# merigold.net
KiCad netlist of a schematic drawn in Altium Designer
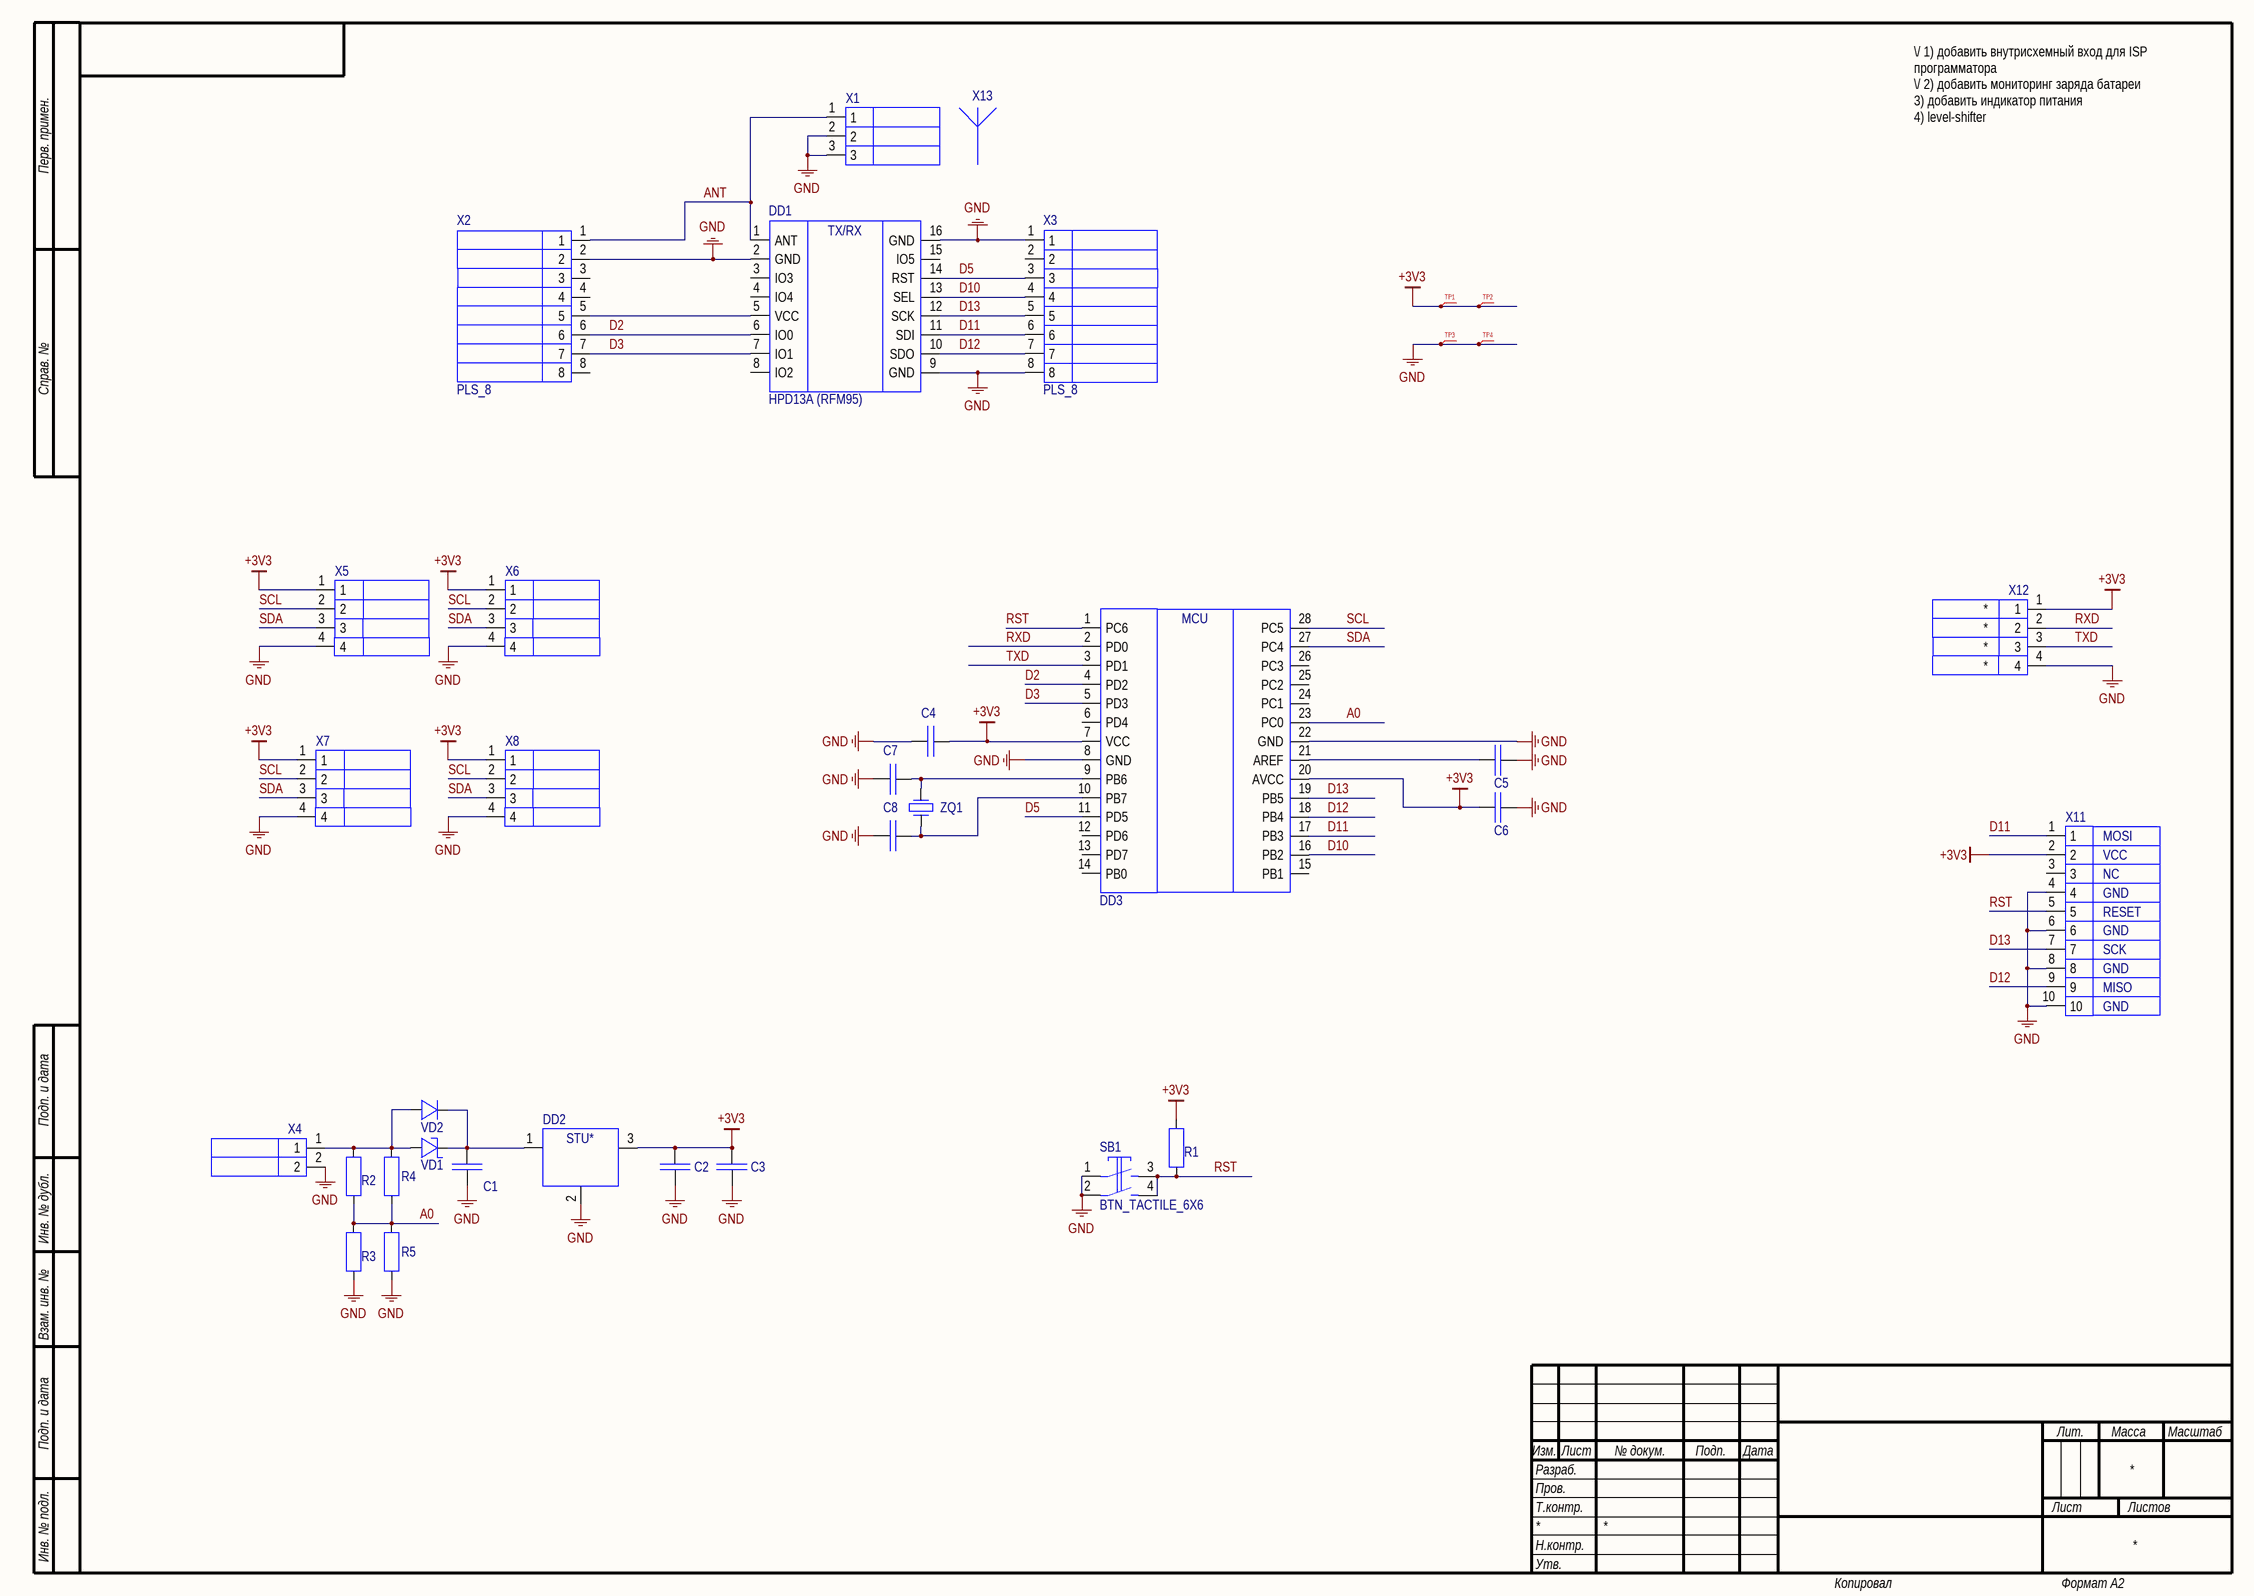
[diagram p0: merigold.SchDoc]

(export (version "E")
  (design (tool "Eeschema 10.0.6"))
  (components
    (comp (ref "C1")
      (value "10U10V_CAPC")
      (footprint "CAPC2012X14M/0805")
      (description "CAP CER 10UF 10V X5R 0805")
      (fields
        (field (name "MANUFACTURER") "Samsung Electro-Mechanics")
        (field (name "MANUFACTURER PART NUMBER") "CL21A106KPFNNNG")
      )
      (libsource (lib "C") (part "10U10V_CAPC"))
    )
    (comp (ref "C2")
      (value "10U10V_CAPC")
      (footprint "CAPC2012X14M/0805")
      (description "CAP CER 10UF 10V X5R 0805")
      (fields
        (field (name "MANUFACTURER") "Samsung Electro-Mechanics")
        (field (name "MANUFACTURER PART NUMBER") "CL21A106KPFNNNG")
      )
      (libsource (lib "C") (part "10U10V_CAPC"))
    )
    (comp (ref "C3")
      (value "1U16V_CAPC")
      (footprint "CAPC2012X14M/0805")
      (description "CAP CER 1UF 16V X7R 0805")
      (fields
        (field (name "MANUFACTURER") "Murata Manufacturing")
        (field (name "MANUFACTURER PART NUMBER") "GRM21BR71C105KA01K")
      )
      (libsource (lib "C") (part "1U16V_CAPC"))
    )
    (comp (ref "C4")
      (value "1U16V_CAPC")
      (footprint "CAPC2012X14M/0805")
      (description "CAP CER 1UF 16V X7R 0805")
      (fields
        (field (name "MANUFACTURER") "Murata Manufacturing")
        (field (name "MANUFACTURER PART NUMBER") "GRM21BR71C105KA01K")
      )
      (libsource (lib "C") (part "1U16V_CAPC"))
    )
    (comp (ref "C5")
      (value "1U16V_CAPC")
      (footprint "CAPC2012X14M/0805")
      (description "CAP CER 1UF 16V X7R 0805")
      (fields
        (field (name "MANUFACTURER") "Murata Manufacturing")
        (field (name "MANUFACTURER PART NUMBER") "GRM21BR71C105KA01K")
      )
      (libsource (lib "C") (part "1U16V_CAPC"))
    )
    (comp (ref "C6")
      (value "1U16V_CAPC")
      (footprint "CAPC2012X14M/0805")
      (description "CAP CER 1UF 16V X7R 0805")
      (fields
        (field (name "MANUFACTURER") "Murata Manufacturing")
        (field (name "MANUFACTURER PART NUMBER") "GRM21BR71C105KA01K")
      )
      (libsource (lib "C") (part "1U16V_CAPC"))
    )
    (comp (ref "C7")
      (value "22P250V_CAPC")
      (footprint "CAPC2012X14M/0805")
      (description "CAP CER 22PF 250V C0G/NP0 0805")
      (fields
        (field (name "MANUFACTURER") "Murata Manufacturing")
        (field (name "MANUFACTURER PART NUMBER") "GRM21A5C2E220JW01")
      )
      (libsource (lib "C") (part "22P250V_CAPC"))
    )
    (comp (ref "C8")
      (value "22P250V_CAPC")
      (footprint "CAPC2012X14M/0805")
      (description "CAP CER 22PF 250V C0G/NP0 0805")
      (fields
        (field (name "MANUFACTURER") "Murata Manufacturing")
        (field (name "MANUFACTURER PART NUMBER") "GRM21A5C2E220JW01")
      )
      (libsource (lib "C") (part "22P250V_CAPC"))
    )
    (comp (ref "DD1")
      (value "HPD13A (RFM95)")
      (footprint "IC:SOJ200P1600X200-16M")
      (description "RF TXRX MODULE ISM<1GHZ")
      (fields
        (field (name "MANUFACTURER") "RF Solutions")
        (field (name "MANUFACTURER PART NUMBER") "RFM95W-868S2")
      )
      (libsource (lib "IC") (part "HPD13A (RFM95)"))
    )
    (comp (ref "DD2")
      (value "LM1117MPX-3.3/NOPB")
      (footprint "SOT230P700X180-4M")
      (description "IC REG LIN 3.3V 800MA SOT223-4")
      (fields (field (name "MANUFACTURER") "Texas Instruments"))
      (libsource (lib "IC") (part "AMS1117"))
    )
    (comp (ref "DD3")
      (value "ATMEGA328")
      (footprint "PDIP28")
      (description "IC MCU 8BIT 32KB FLASH 28DIP")
      (fields
        (field (name "MANUFACTURER") "Microchip / Atmel")
        (field (name "MANUFACTURER PART NUMBER") "ATMEGA328P-PU")
      )
      (libsource (lib "IC") (part "ATMEGA328P-PU"))
    )
    (comp (ref "R1")
      (value "10K1206")
      (footprint "RLC:RESC3216X07N/1206")
      (description "RES SMD 10K OHM 1% 1/4W 1206")
      (fields
        (field (name "MANUFACTURER") "Panasonic")
        (field (name "MANUFACTURER PART NUMBER") "ERJ8ENF1002V")
      )
      (libsource (lib "R") (part "10K1206"))
    )
    (comp (ref "R2")
      (value "RNF14FTD100K")
      (footprint "RESAD800W55L600D230")
      (description "RES 100K OHM 1/4W 5% AXIAL")
      (fields (field (name "MANUFACTURER") "Stackpole Electronics"))
      (libsource (lib "R") (part "100K_AD800W55L600D230"))
    )
    (comp (ref "R3")
      (value "RNF14FTD100K")
      (footprint "RESAD800W55L600D230")
      (description "RES 100K OHM 1/4W 5% AXIAL")
      (fields (field (name "MANUFACTURER") "Stackpole Electronics"))
      (libsource (lib "R") (part "100K_AD800W55L600D230"))
    )
    (comp (ref "R4")
      (value "100K0603")
      (footprint "RESC1608X06N/0603")
      (description "RES SMD 100K OHM 1% 1/4W 0603")
      (fields (field (name "MANUFACTURER PART NUMBER") "ESR03EZPF1003"))
      (libsource (lib "R") (part "100K0603"))
    )
    (comp (ref "R5")
      (value "100K0603")
      (footprint "RESC1608X06N/0603")
      (description "RES SMD 100K OHM 1% 1/4W 0603")
      (fields (field (name "MANUFACTURER PART NUMBER") "ESR03EZPF1003"))
      (libsource (lib "R") (part "100K0603"))
    )
    (comp (ref "SB1")
      (value "BTN_TACTILE_6X6")
      (footprint "BTN_TACTILE_6X6")
      (description "SWITCH TACTILE SPST-NO 0.05A 24V")
      (fields
        (field (name "MANUFACTURER") "TE Connectivity Alcoswitch")
        (field (name "MANUFACTURER PART NUMBER") "1825910-6")
      )
      (libsource (lib "SW") (part "BTN_TACTILE_6X6"))
    )
    (comp (ref "TP1")
      (value "TP_TH")
      (footprint "TH_TP")
      (description "TEST POINT THROUGH HOLE")
      (libsource (lib "X") (part "TP_TH"))
    )
    (comp (ref "TP2")
      (value "TP_TH")
      (footprint "TH_TP")
      (description "TEST POINT THROUGH HOLE")
      (libsource (lib "X") (part "TP_TH"))
    )
    (comp (ref "TP3")
      (value "TP_TH")
      (footprint "TH_TP")
      (description "TEST POINT THROUGH HOLE")
      (libsource (lib "X") (part "TP_TH"))
    )
    (comp (ref "TP4")
      (value "TP_TH")
      (footprint "TH_TP")
      (description "TEST POINT THROUGH HOLE")
      (libsource (lib "X") (part "TP_TH"))
    )
    (comp (ref "VD1")
      (value "MBR120VLSFT1G")
      (footprint "SOD-123")
      (description "DIODE SCHOTTKY 20V 1A SOD123FL")
      (fields (field (name "MANUFACTURER") "ON Semiconductor"))
      (libsource (lib "D") (part "MBR120VLSFT1G"))
    )
    (comp (ref "VD2")
      (value "HER107G R0G")
      (footprint "DO-204AL")
      (description "DIODE GEN PURP 800V 1A DO204AL")
      (fields (field (name "MANUFACTURER") "Taiwan Semiconductor Corporation"))
      (libsource (lib "D") (part "HER107G R0G"))
    )
    (comp (ref "X1")
      (value "U.FL-R-SMT-1_sch")
      (footprint "U.FL-R-SMT-1")
      (description "CONN U.FL RCPT STR 50 OHM SMD")
      (fields
        (field (name "MANUFACTURER") "Hirose")
        (field (name "MANUFACTURER PART NUMBER") "U.FL-R-SMT-1(10)")
      )
      (libsource (lib "ANT") (part "U.FL-R-SMT-1_sch"))
    )
    (comp (ref "X2")
      (value "PLS_8")
      (footprint "PLS_8")
      (description "CONN HEADER VERT 8POS 2.54MM")
      (fields (field (name "MANUFACTURER") "Harwin") (field (name "MANUFACTURER PART NUMBER") "M20-7820842"))
      (libsource (lib "X") (part "PLS_8"))
    )
    (comp (ref "X3")
      (value "PLS_8")
      (footprint "PLS_8")
      (description "CONN HEADER VERT 8POS 2.54MM")
      (fields (field (name "MANUFACTURER") "Harwin") (field (name "MANUFACTURER PART NUMBER") "M20-7820842"))
      (libsource (lib "X") (part "PLS_8"))
    )
    (comp (ref "X4")
      (value "2EDGV-5.0-02P")
      (footprint "2EDGV-5.0-02P")
      (description "TERM BLOCK HDR 2POS VERT 5MM")
      (fields
        (field (name "MANUFACTURER") "Phoenix Contact")
        (field (name "MANUFACTURER PART NUMBER") "1753437")
      )
      (libsource (lib "X") (part "2EDGV-5.0-02P"))
    )
    (comp (ref "X5")
      (value "2EDGV-5.0-04P")
      (footprint "2EDGV-5.0-04P")
      (description "TERM BLOCK HDR 4POS VERT 5MM")
      (fields
        (field (name "MANUFACTURER") "Phoenix Contact")
        (field (name "MANUFACTURER PART NUMBER") "1753479")
      )
      (libsource (lib "X") (part "2EDGV-5.0-04P"))
    )
    (comp (ref "X6")
      (value "2EDGV-5.0-04P")
      (footprint "2EDGV-5.0-04P")
      (description "TERM BLOCK HDR 4POS VERT 5MM")
      (fields
        (field (name "MANUFACTURER") "Phoenix Contact")
        (field (name "MANUFACTURER PART NUMBER") "1753479")
      )
      (libsource (lib "X") (part "2EDGV-5.0-04P"))
    )
    (comp (ref "X7")
      (value "2EDGV-5.0-04P")
      (footprint "2EDGV-5.0-04P")
      (description "TERM BLOCK HDR 4POS VERT 5MM")
      (fields
        (field (name "MANUFACTURER") "Phoenix Contact")
        (field (name "MANUFACTURER PART NUMBER") "1753479")
      )
      (libsource (lib "X") (part "2EDGV-5.0-04P"))
    )
    (comp (ref "X8")
      (value "2EDGV-5.0-04P")
      (footprint "2EDGV-5.0-04P")
      (description "TERM BLOCK HDR 4POS VERT 5MM")
      (fields
        (field (name "MANUFACTURER") "Phoenix Contact")
        (field (name "MANUFACTURER PART NUMBER") "1753479")
      )
      (libsource (lib "X") (part "2EDGV-5.0-04P"))
    )
    (comp (ref "X11")
      (value "ISP")
      (footprint "302_SERIES_10POS")
      (description "CONN HEADER VERT 10POS 2.54MM")
      (fields
        (field (name "MANUFACTURERPARTNUMBER") "302-S101")
        (field (name "MANUFACTURER") "On-Shore Technology")
      )
      (libsource (lib "X") (part "ISP"))
    )
    (comp (ref "X12")
      (value "61300411121")
      (footprint "PLS_4")
      (description "CONN HEADER VERT 4POS 2.54MM")
      (fields
        (field (name "MANUFACTURER") "Wurth Electronics")
        (field (name "1") "*")
        (field (name "2") "*")
        (field (name "3") "*")
        (field (name "4") "*")
      )
      (libsource (lib "X") (part "PLS_4"))
    )
    (comp (ref "X13")
      (value "ANT-8WPIG-UFL")
      (description "RF ANT 868MHZ WHIP STR U.FL 50MM")
      (fields (field (name "MANUFACTURER") "RF Solutions"))
      (libsource (lib "ANT") (part "ANT-8WPIG-UFL"))
    )
    (comp (ref "ZQ1")
      (value "HC49U-8-30-50-70-30-ATF")
      (footprint "XTAL1050X465X350")
      (description "CRYSTAL 8.0MHZ 30PF SMD")
      (fields (field (name "MANUFACTURER") "IQD Frequency Products"))
      (libsource (lib "XTAL") (part "HC49U-8-30-50-70-30-ATF"))
    )
  )
  (nets
    (net (code "1") (name "+3V3") (class "Default")
      (node (ref "C2") (pin "2") (pinfunction "2_2") (pintype "passive"))
      (node (ref "C3") (pin "2") (pinfunction "2_2") (pintype "passive"))
      (node (ref "C4") (pin "2") (pinfunction "2_2") (pintype "passive"))
      (node (ref "C6") (pin "1") (pinfunction "1_1") (pintype "passive"))
      (node (ref "DD2") (pin "3") (pinfunction "OUT_3") (pintype "passive"))
      (node (ref "DD3") (pin "20") (pinfunction "AVCC_20") (pintype "passive"))
      (node (ref "DD3") (pin "7") (pinfunction "VCC_7") (pintype "passive"))
      (node (ref "R1") (pin "2") (pinfunction "2_2") (pintype "passive"))
      (node (ref "TP1") (pin "1") (pinfunction "TP_1") (pintype "passive"))
      (node (ref "TP2") (pin "1") (pinfunction "TP_1") (pintype "passive"))
      (node (ref "X11") (pin "2") (pinfunction "2_2") (pintype "passive"))
      (node (ref "X12") (pin "1") (pinfunction "1_1") (pintype "passive"))
      (node (ref "X5") (pin "1") (pinfunction "1_1") (pintype "passive"))
      (node (ref "X6") (pin "1") (pinfunction "1_1") (pintype "passive"))
      (node (ref "X7") (pin "1") (pinfunction "1_1") (pintype "passive"))
      (node (ref "X8") (pin "1") (pinfunction "1_1") (pintype "passive"))
    )
    (net (code "2") (name "/A0") (class "Default")
      (node (ref "DD3") (pin "23") (pinfunction "PC0_23") (pintype "passive"))
      (node (ref "R2") (pin "1") (pinfunction "1_1") (pintype "passive"))
      (node (ref "R3") (pin "2") (pinfunction "2_2") (pintype "passive"))
      (node (ref "R4") (pin "1") (pinfunction "1_1") (pintype "passive"))
      (node (ref "R5") (pin "2") (pinfunction "2_2") (pintype "passive"))
    )
    (net (code "3") (name "/ANT") (class "Default")
      (node (ref "DD1") (pin "1") (pinfunction "ANT_1") (pintype "passive"))
      (node (ref "X1") (pin "1") (pinfunction "1_1") (pintype "passive"))
      (node (ref "X2") (pin "1") (pinfunction "1_1") (pintype "passive"))
    )
    (net (code "4") (name "/D2") (class "Default")
      (node (ref "DD1") (pin "6") (pinfunction "IO0_6") (pintype "passive"))
      (node (ref "DD3") (pin "4") (pinfunction "PD2_4") (pintype "passive"))
      (node (ref "X2") (pin "6") (pinfunction "6_6") (pintype "passive"))
    )
    (net (code "5") (name "/D3") (class "Default")
      (node (ref "DD1") (pin "7") (pinfunction "IO1_7") (pintype "passive"))
      (node (ref "DD3") (pin "5") (pinfunction "PD3_5") (pintype "passive"))
      (node (ref "X2") (pin "7") (pinfunction "7_7") (pintype "passive"))
    )
    (net (code "6") (name "/D5") (class "Default")
      (node (ref "DD1") (pin "14") (pinfunction "RST_14") (pintype "passive"))
      (node (ref "DD3") (pin "11") (pinfunction "PD5_11") (pintype "passive"))
      (node (ref "X3") (pin "3") (pinfunction "3_3") (pintype "passive"))
    )
    (net (code "7") (name "/D10") (class "Default")
      (node (ref "DD1") (pin "13") (pinfunction "SEL_13") (pintype "passive"))
      (node (ref "DD3") (pin "16") (pinfunction "PB2_16") (pintype "passive"))
      (node (ref "X3") (pin "4") (pinfunction "4_4") (pintype "passive"))
    )
    (net (code "8") (name "/D11") (class "Default")
      (node (ref "DD1") (pin "11") (pinfunction "SDI_11") (pintype "passive"))
      (node (ref "DD3") (pin "17") (pinfunction "PB3_17") (pintype "passive"))
      (node (ref "X11") (pin "1") (pinfunction "1_1") (pintype "passive"))
      (node (ref "X3") (pin "6") (pinfunction "6_6") (pintype "passive"))
    )
    (net (code "9") (name "/D12") (class "Default")
      (node (ref "DD1") (pin "10") (pinfunction "SDO_10") (pintype "passive"))
      (node (ref "DD3") (pin "18") (pinfunction "PB4_18") (pintype "passive"))
      (node (ref "X11") (pin "9") (pinfunction "9_9") (pintype "passive"))
      (node (ref "X3") (pin "7") (pinfunction "7_7") (pintype "passive"))
    )
    (net (code "10") (name "/D13") (class "Default")
      (node (ref "DD1") (pin "12") (pinfunction "SCK_12") (pintype "passive"))
      (node (ref "DD3") (pin "19") (pinfunction "PB5_19") (pintype "passive"))
      (node (ref "X11") (pin "7") (pinfunction "7_7") (pintype "passive"))
      (node (ref "X3") (pin "5") (pinfunction "5_5") (pintype "passive"))
    )
    (net (code "11") (name "/RST") (class "Default")
      (node (ref "DD3") (pin "1") (pinfunction "PC6_1") (pintype "passive"))
      (node (ref "R1") (pin "1") (pinfunction "1_1") (pintype "passive"))
      (node (ref "SB1") (pin "3") (pinfunction "3_3") (pintype "passive"))
      (node (ref "SB1") (pin "4") (pinfunction "4_4") (pintype "passive"))
      (node (ref "X11") (pin "5") (pinfunction "5_5") (pintype "passive"))
    )
    (net (code "12") (name "/RXD") (class "Default")
      (node (ref "DD3") (pin "2") (pinfunction "PD0_2") (pintype "passive"))
      (node (ref "X12") (pin "2") (pinfunction "2_2") (pintype "passive"))
    )
    (net (code "13") (name "/SCL") (class "Default")
      (node (ref "DD3") (pin "28") (pinfunction "PC5_28") (pintype "passive"))
      (node (ref "X5") (pin "2") (pinfunction "2_2") (pintype "passive"))
      (node (ref "X6") (pin "2") (pinfunction "2_2") (pintype "passive"))
      (node (ref "X7") (pin "2") (pinfunction "2_2") (pintype "passive"))
      (node (ref "X8") (pin "2") (pinfunction "2_2") (pintype "passive"))
    )
    (net (code "14") (name "/SDA") (class "Default")
      (node (ref "DD3") (pin "27") (pinfunction "PC4_27") (pintype "passive"))
      (node (ref "X5") (pin "3") (pinfunction "3_3") (pintype "passive"))
      (node (ref "X6") (pin "3") (pinfunction "3_3") (pintype "passive"))
      (node (ref "X7") (pin "3") (pinfunction "3_3") (pintype "passive"))
      (node (ref "X8") (pin "3") (pinfunction "3_3") (pintype "passive"))
    )
    (net (code "15") (name "/TXD") (class "Default")
      (node (ref "DD3") (pin "3") (pinfunction "PD1_3") (pintype "passive"))
      (node (ref "X12") (pin "3") (pinfunction "3_3") (pintype "passive"))
    )
    (net (code "16") (name "GND") (class "Default")
      (node (ref "C1") (pin "1") (pinfunction "1_1") (pintype "passive"))
      (node (ref "C2") (pin "1") (pinfunction "1_1") (pintype "passive"))
      (node (ref "C3") (pin "1") (pinfunction "1_1") (pintype "passive"))
      (node (ref "C4") (pin "1") (pinfunction "1_1") (pintype "passive"))
      (node (ref "C5") (pin "2") (pinfunction "2_2") (pintype "passive"))
      (node (ref "C6") (pin "2") (pinfunction "2_2") (pintype "passive"))
      (node (ref "C7") (pin "1") (pinfunction "1_1") (pintype "passive"))
      (node (ref "C8") (pin "1") (pinfunction "1_1") (pintype "passive"))
      (node (ref "DD1") (pin "16") (pinfunction "GND_16") (pintype "passive"))
      (node (ref "DD1") (pin "2") (pinfunction "GND_2") (pintype "passive"))
      (node (ref "DD1") (pin "9") (pinfunction "GND_9") (pintype "passive"))
      (node (ref "DD2") (pin "2") (pinfunction "GND_2") (pintype "passive"))
      (node (ref "DD3") (pin "22") (pinfunction "GND_22") (pintype "passive"))
      (node (ref "DD3") (pin "8") (pinfunction "GND_8") (pintype "passive"))
      (node (ref "R3") (pin "1") (pinfunction "1_1") (pintype "passive"))
      (node (ref "R5") (pin "1") (pinfunction "1_1") (pintype "passive"))
      (node (ref "SB1") (pin "1") (pinfunction "1_1") (pintype "passive"))
      (node (ref "SB1") (pin "2") (pinfunction "2_2") (pintype "passive"))
      (node (ref "TP3") (pin "1") (pinfunction "TP_1") (pintype "passive"))
      (node (ref "TP4") (pin "1") (pinfunction "TP_1") (pintype "passive"))
      (node (ref "X1") (pin "2") (pinfunction "2_2") (pintype "passive"))
      (node (ref "X1") (pin "3") (pinfunction "3_3") (pintype "passive"))
      (node (ref "X11") (pin "10") (pinfunction "10_10") (pintype "passive"))
      (node (ref "X11") (pin "4") (pinfunction "4_4") (pintype "passive"))
      (node (ref "X11") (pin "6") (pinfunction "6_6") (pintype "passive"))
      (node (ref "X11") (pin "8") (pinfunction "8_8") (pintype "passive"))
      (node (ref "X12") (pin "4") (pinfunction "4_4") (pintype "passive"))
      (node (ref "X2") (pin "2") (pinfunction "2_2") (pintype "passive"))
      (node (ref "X3") (pin "1") (pinfunction "1_1") (pintype "passive"))
      (node (ref "X3") (pin "8") (pinfunction "8_8") (pintype "passive"))
      (node (ref "X4") (pin "2") (pinfunction "2_2") (pintype "passive"))
      (node (ref "X5") (pin "4") (pinfunction "4_4") (pintype "passive"))
      (node (ref "X6") (pin "4") (pinfunction "4_4") (pintype "passive"))
      (node (ref "X7") (pin "4") (pinfunction "4_4") (pintype "passive"))
      (node (ref "X8") (pin "4") (pinfunction "4_4") (pintype "passive"))
    )
    (net (code "17") (name "Net-(DD1-VCC)") (class "Default")
      (node (ref "DD1") (pin "5") (pinfunction "VCC_5") (pintype "passive"))
      (node (ref "X2") (pin "5") (pinfunction "5_5") (pintype "passive"))
    )
    (net (code "18") (name "Net-(DD2-IN)") (class "Default")
      (node (ref "C1") (pin "2") (pinfunction "2_2") (pintype "passive"))
      (node (ref "DD2") (pin "1") (pinfunction "IN_1") (pintype "passive"))
      (node (ref "VD1") (pin "K") (pinfunction "K_K") (pintype "passive"))
      (node (ref "VD2") (pin "K") (pinfunction "K_K") (pintype "passive"))
    )
    (net (code "19") (name "Net-(DD3-AREF)") (class "Default")
      (node (ref "C5") (pin "1") (pinfunction "1_1") (pintype "passive"))
      (node (ref "DD3") (pin "21") (pinfunction "AREF_21") (pintype "passive"))
    )
    (net (code "20") (name "Net-(DD3-PB6)") (class "Default")
      (node (ref "C7") (pin "2") (pinfunction "2_2") (pintype "passive"))
      (node (ref "DD3") (pin "9") (pinfunction "PB6_9") (pintype "passive"))
      (node (ref "ZQ1") (pin "2") (pinfunction "2_2") (pintype "passive"))
    )
    (net (code "21") (name "Net-(DD3-PB7)") (class "Default")
      (node (ref "C8") (pin "2") (pinfunction "2_2") (pintype "passive"))
      (node (ref "DD3") (pin "10") (pinfunction "PB7_10") (pintype "passive"))
      (node (ref "ZQ1") (pin "1") (pinfunction "1_1") (pintype "passive"))
    )
    (net (code "22") (name "Net-(R2-Pad2)") (class "Default")
      (node (ref "R2") (pin "2") (pinfunction "2_2") (pintype "passive"))
      (node (ref "R4") (pin "2") (pinfunction "2_2") (pintype "passive"))
      (node (ref "VD1") (pin "A") (pinfunction "A_A") (pintype "passive"))
      (node (ref "VD2") (pin "A") (pinfunction "A_A") (pintype "passive"))
      (node (ref "X4") (pin "1") (pinfunction "1_1") (pintype "passive"))
    )
    (net (code "23") (name "unconnected-(DD1-IO2-Pad8)") (class "Default")
      (node (ref "DD1") (pin "8") (pinfunction "IO2_8") (pintype "passive"))
    )
    (net (code "24") (name "unconnected-(DD1-IO3-Pad3)") (class "Default")
      (node (ref "DD1") (pin "3") (pinfunction "IO3_3") (pintype "passive"))
    )
    (net (code "25") (name "unconnected-(DD1-IO4-Pad4)") (class "Default")
      (node (ref "DD1") (pin "4") (pinfunction "IO4_4") (pintype "passive"))
    )
    (net (code "26") (name "unconnected-(DD1-IO5-Pad15)") (class "Default")
      (node (ref "DD1") (pin "15") (pinfunction "IO5_15") (pintype "passive"))
    )
    (net (code "27") (name "unconnected-(DD3-PB0-Pad14)") (class "Default")
      (node (ref "DD3") (pin "14") (pinfunction "PB0_14") (pintype "passive"))
    )
    (net (code "28") (name "unconnected-(DD3-PB1-Pad15)") (class "Default")
      (node (ref "DD3") (pin "15") (pinfunction "PB1_15") (pintype "passive"))
    )
    (net (code "29") (name "unconnected-(DD3-PC1-Pad24)") (class "Default")
      (node (ref "DD3") (pin "24") (pinfunction "PC1_24") (pintype "passive"))
    )
    (net (code "30") (name "unconnected-(DD3-PC2-Pad25)") (class "Default")
      (node (ref "DD3") (pin "25") (pinfunction "PC2_25") (pintype "passive"))
    )
    (net (code "31") (name "unconnected-(DD3-PC3-Pad26)") (class "Default")
      (node (ref "DD3") (pin "26") (pinfunction "PC3_26") (pintype "passive"))
    )
    (net (code "32") (name "unconnected-(DD3-PD4-Pad6)") (class "Default")
      (node (ref "DD3") (pin "6") (pinfunction "PD4_6") (pintype "passive"))
    )
    (net (code "33") (name "unconnected-(DD3-PD6-Pad12)") (class "Default")
      (node (ref "DD3") (pin "12") (pinfunction "PD6_12") (pintype "passive"))
    )
    (net (code "34") (name "unconnected-(DD3-PD7-Pad13)") (class "Default")
      (node (ref "DD3") (pin "13") (pinfunction "PD7_13") (pintype "passive"))
    )
    (net (code "35") (name "unconnected-(X2-Pad3)") (class "Default")
      (node (ref "X2") (pin "3") (pinfunction "3_3") (pintype "passive"))
    )
    (net (code "36") (name "unconnected-(X2-Pad4)") (class "Default")
      (node (ref "X2") (pin "4") (pinfunction "4_4") (pintype "passive"))
    )
    (net (code "37") (name "unconnected-(X2-Pad8)") (class "Default")
      (node (ref "X2") (pin "8") (pinfunction "8_8") (pintype "passive"))
    )
    (net (code "38") (name "unconnected-(X3-Pad2)") (class "Default")
      (node (ref "X3") (pin "2") (pinfunction "2_2") (pintype "passive"))
    )
    (net (code "39") (name "unconnected-(X11-Pad3)") (class "Default")
      (node (ref "X11") (pin "3") (pinfunction "3_3") (pintype "passive"))
    )
  )
)
